# k26_baseboard_connectors2.net
KiCad netlist of a schematic drawn in Altium Designer
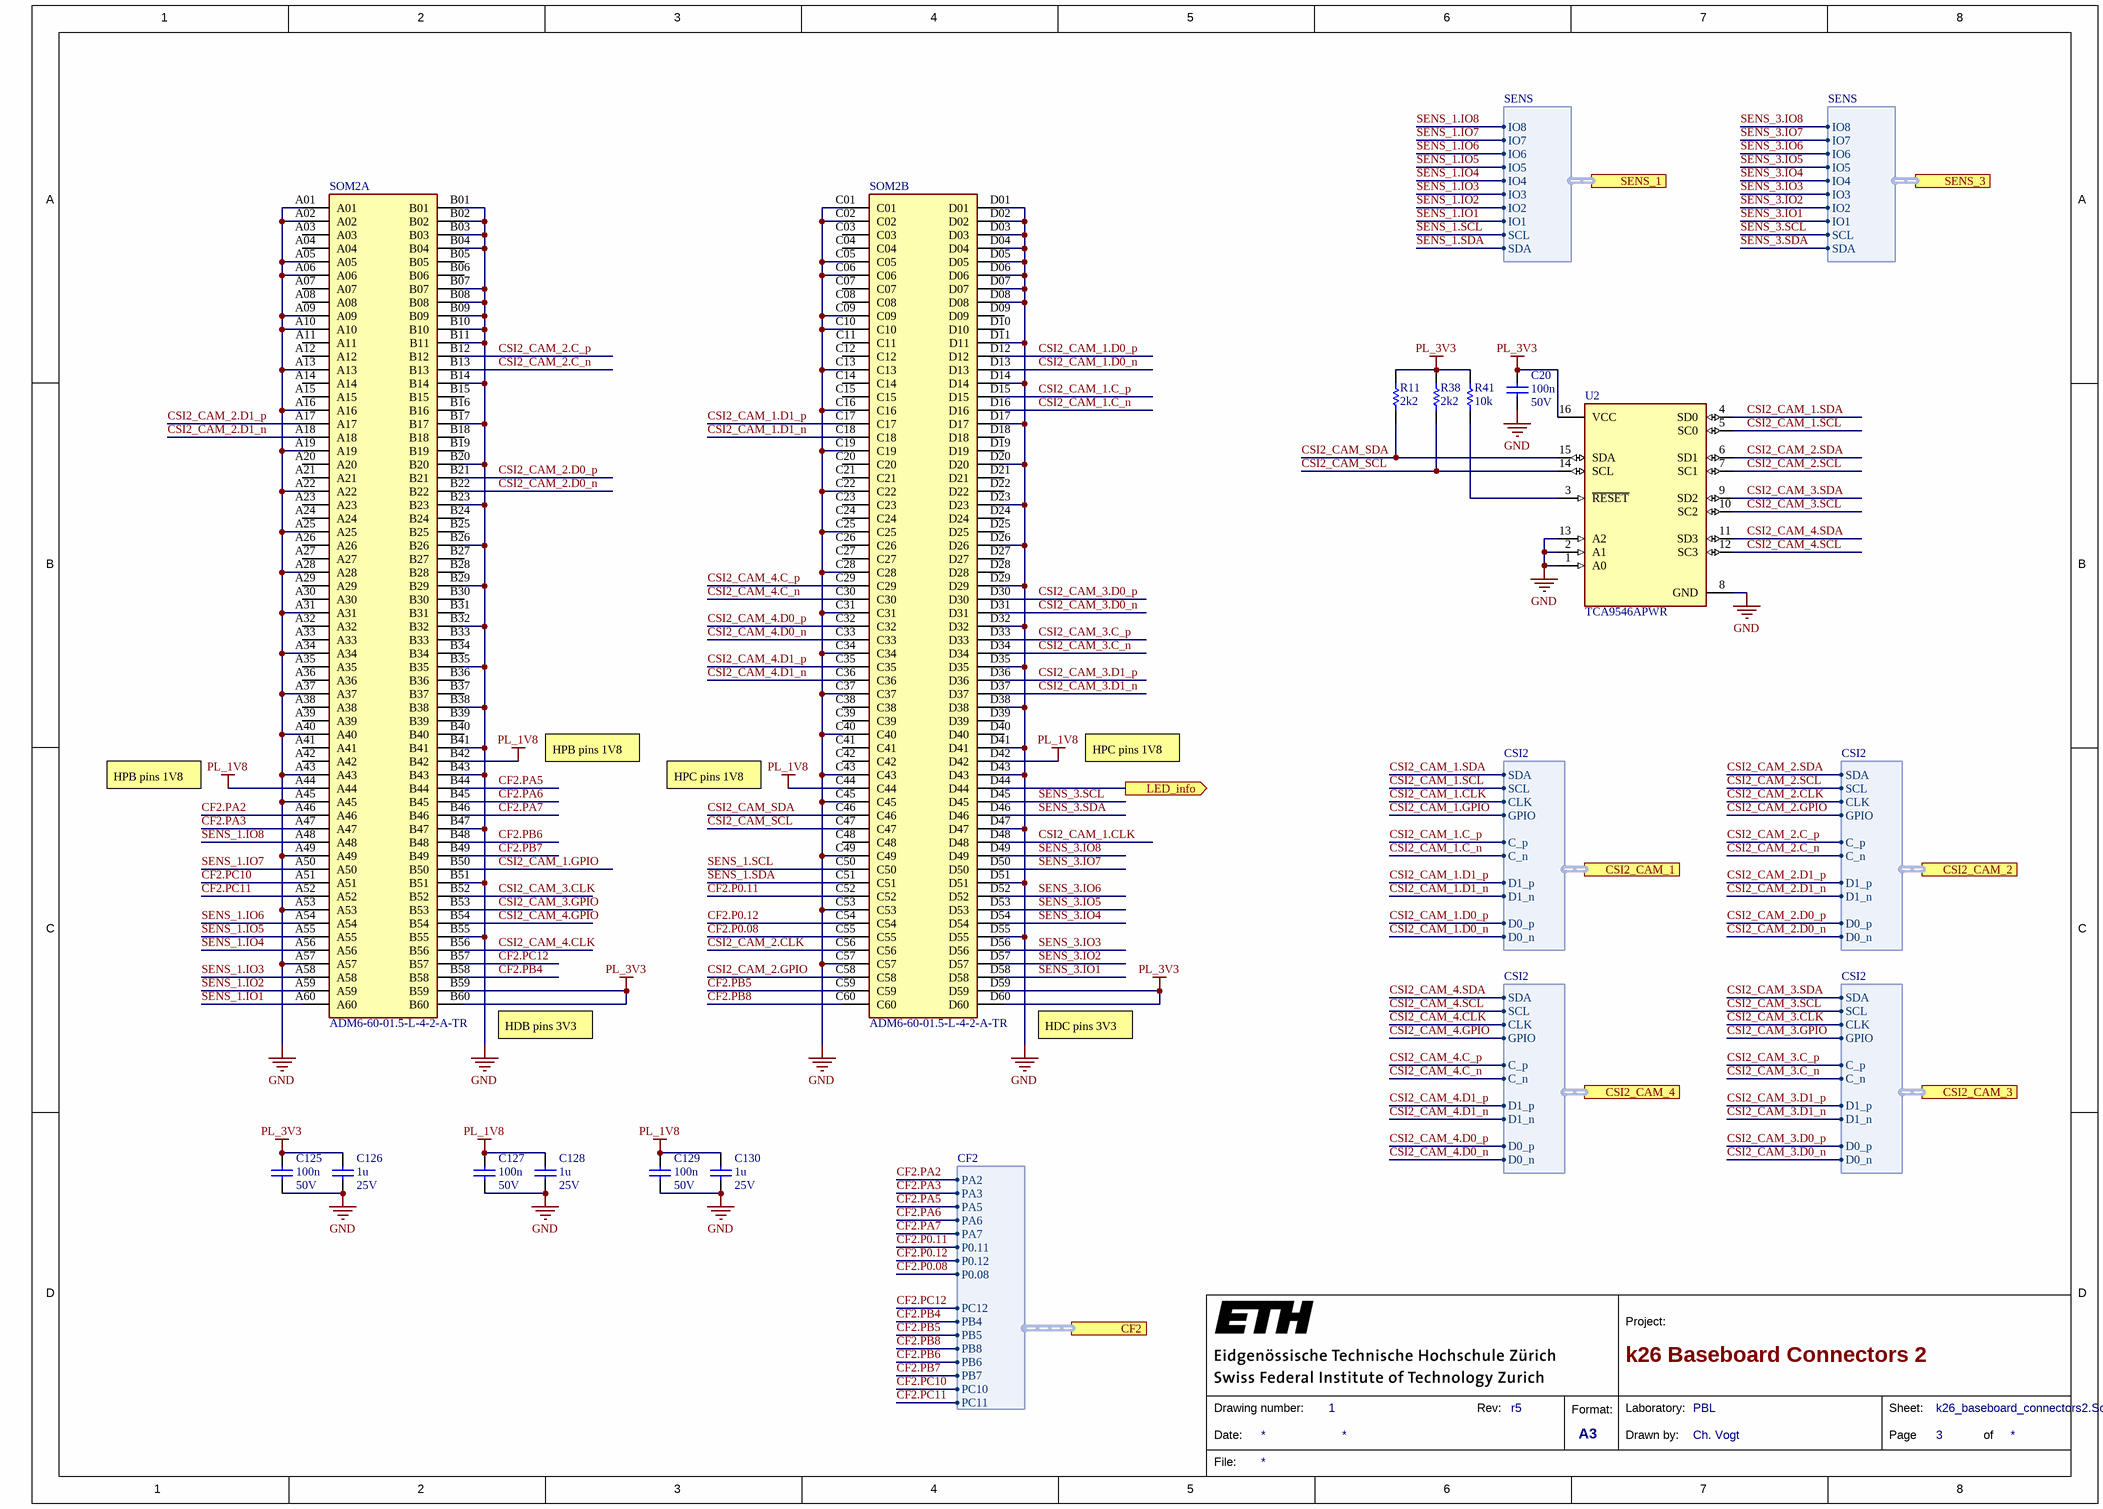
[diagram p0: k26_baseboard_connectors2.SchDoc]

(export (version "E")
  (design (tool "Eeschema 10.0.6"))
  (components
    (comp (ref "C20")
      (value "100n")
      (footprint "k26_FPGA_drone_baseboard:CAPC0402")
      (fields
        (field (name "MANUFACTURER") "Yageo")
        (field (name "MANUFACTURER PART NUMBER") "CC0402KRX5R9BB104")
        (field (name "RATED DC VOLTAGE (URDC)") "50V")
      )
      (libsource (lib "k26_FPGA_drone_baseboard") (part "cap0402"))
    )
    (comp (ref "C125")
      (value "100n")
      (footprint "k26_FPGA_drone_baseboard:CAPC0402")
      (fields
        (field (name "MANUFACTURER") "Yageo")
        (field (name "MANUFACTURER PART NUMBER") "CC0402KRX5R9BB104")
        (field (name "RATED DC VOLTAGE (URDC)") "50V")
      )
      (libsource (lib "k26_FPGA_drone_baseboard") (part "cap0402"))
    )
    (comp (ref "C126")
      (value "1u")
      (footprint "k26_FPGA_drone_baseboard:CAPC0402")
      (fields
        (field (name "MANUFACTURER") "Taiyo Yuden")
        (field (name "MANUFACTURER PART NUMBER") "TMK105BJ105MV-F")
        (field (name "RATED DC VOLTAGE (URDC)") "25V")
      )
      (libsource (lib "k26_FPGA_drone_baseboard") (part "cap0402"))
    )
    (comp (ref "C127")
      (value "100n")
      (footprint "k26_FPGA_drone_baseboard:CAPC0402")
      (fields
        (field (name "MANUFACTURER") "Yageo")
        (field (name "MANUFACTURER PART NUMBER") "CC0402KRX5R9BB104")
        (field (name "RATED DC VOLTAGE (URDC)") "50V")
      )
      (libsource (lib "k26_FPGA_drone_baseboard") (part "cap0402"))
    )
    (comp (ref "C128")
      (value "1u")
      (footprint "k26_FPGA_drone_baseboard:CAPC0402")
      (fields
        (field (name "MANUFACTURER") "Taiyo Yuden")
        (field (name "MANUFACTURER PART NUMBER") "TMK105BJ105MV-F")
        (field (name "RATED DC VOLTAGE (URDC)") "25V")
      )
      (libsource (lib "k26_FPGA_drone_baseboard") (part "cap0402"))
    )
    (comp (ref "C129")
      (value "100n")
      (footprint "k26_FPGA_drone_baseboard:CAPC0402")
      (fields
        (field (name "MANUFACTURER") "Yageo")
        (field (name "MANUFACTURER PART NUMBER") "CC0402KRX5R9BB104")
        (field (name "RATED DC VOLTAGE (URDC)") "50V")
      )
      (libsource (lib "k26_FPGA_drone_baseboard") (part "cap0402"))
    )
    (comp (ref "C130")
      (value "1u")
      (footprint "k26_FPGA_drone_baseboard:CAPC0402")
      (fields
        (field (name "MANUFACTURER") "Taiyo Yuden")
        (field (name "MANUFACTURER PART NUMBER") "TMK105BJ105MV-F")
        (field (name "RATED DC VOLTAGE (URDC)") "25V")
      )
      (libsource (lib "k26_FPGA_drone_baseboard") (part "cap0402"))
    )
    (comp (ref "R11")
      (value "2k2")
      (footprint "k26_FPGA_drone_baseboard:RES0402")
      (fields
        (field (name "MANUFACTURER") "Vishay")
        (field (name "MANUFACTURER PART NUMBER") "CRCW04022K20FKED")
        (field (name "TOLERANCE") "1%")
      )
      (libsource (lib "k26_FPGA_drone_baseboard") (part "res0402"))
    )
    (comp (ref "R38")
      (value "2k2")
      (footprint "k26_FPGA_drone_baseboard:RES0402")
      (fields
        (field (name "MANUFACTURER") "Vishay")
        (field (name "MANUFACTURER PART NUMBER") "CRCW04022K20FKED")
        (field (name "TOLERANCE") "1%")
      )
      (libsource (lib "k26_FPGA_drone_baseboard") (part "res0402"))
    )
    (comp (ref "R41")
      (value "10k")
      (footprint "k26_FPGA_drone_baseboard:RES0402")
      (fields
        (field (name "MANUFACTURER") "Panasonic")
        (field (name "MANUFACTURER PART NUMBER") "ERJ-2RKF1002X")
        (field (name "TOLERANCE") "1%")
      )
      (libsource (lib "k26_FPGA_drone_baseboard") (part "res0402"))
    )
    (comp (ref "SOM2")
      (value "ADM6-60-01.5-L-4-2-A-TR")
      (footprint "k26_FPGA_drone_baseboard:SAMTEC_ADM6-60-01.5-L-4-2-A-TR")
      (description "0.635 mm AcceleRate HD High-Density 4-Row Header")
      (libsource (lib "k26_FPGA_drone_baseboard") (part "ADM6-60-01.5-L-4-2-A-TR"))
    )
    (comp (ref "U2")
      (value "TCA9546APWR")
      (footprint "FP-PW0016A-MFG")
      (description "IC I2C SW 4CH W/RESET 16TSSOP")
      (fields
        (field (name "MANUFACTURER") "Texas Instruments")
        (field (name "OCTOPART") "https://octopart.com/tca9546apwr-texas+instruments-22292132")
      )
      (libsource (lib "Altium Content Vault") (part "b52764720d55b156f509f767142d035"))
    )
  )
  (nets
    (net (code "4") (name "/CF2.P0.08") (class "Default")
      (node (ref "SOM2") (pin "C55") (pinfunction "C55_C55") (pintype "passive"))
    )
    (net (code "5") (name "/CF2.P0.11") (class "Default")
      (node (ref "SOM2") (pin "C52") (pinfunction "C52_C52") (pintype "passive"))
    )
    (net (code "6") (name "/CF2.P0.12") (class "Default")
      (node (ref "SOM2") (pin "C54") (pinfunction "C54_C54") (pintype "passive"))
    )
    (net (code "7") (name "/CF2.PA2") (class "Default")
      (node (ref "SOM2") (pin "A46") (pinfunction "A46_A46") (pintype "passive"))
    )
    (net (code "8") (name "/CF2.PA3") (class "Default")
      (node (ref "SOM2") (pin "A47") (pinfunction "A47_A47") (pintype "passive"))
    )
    (net (code "9") (name "/CF2.PA5") (class "Default")
      (node (ref "SOM2") (pin "B44") (pinfunction "B44_B44") (pintype "passive"))
    )
    (net (code "10") (name "/CF2.PA6") (class "Default")
      (node (ref "SOM2") (pin "B45") (pinfunction "B45_B45") (pintype "passive"))
    )
    (net (code "11") (name "/CF2.PA7") (class "Default")
      (node (ref "SOM2") (pin "B46") (pinfunction "B46_B46") (pintype "passive"))
    )
    (net (code "12") (name "/CF2.PB4") (class "Default")
      (node (ref "SOM2") (pin "B58") (pinfunction "B58_B58") (pintype "passive"))
    )
    (net (code "13") (name "/CF2.PB5") (class "Default")
      (node (ref "SOM2") (pin "C59") (pinfunction "C59_C59") (pintype "passive"))
    )
    (net (code "14") (name "/CF2.PB6") (class "Default")
      (node (ref "SOM2") (pin "B48") (pinfunction "B48_B48") (pintype "passive"))
    )
    (net (code "15") (name "/CF2.PB7") (class "Default")
      (node (ref "SOM2") (pin "B49") (pinfunction "B49_B49") (pintype "passive"))
    )
    (net (code "16") (name "/CF2.PB8") (class "Default")
      (node (ref "SOM2") (pin "C60") (pinfunction "C60_C60") (pintype "passive"))
    )
    (net (code "17") (name "/CF2.PC10") (class "Default")
      (node (ref "SOM2") (pin "A51") (pinfunction "A51_A51") (pintype "passive"))
    )
    (net (code "18") (name "/CF2.PC11") (class "Default")
      (node (ref "SOM2") (pin "A52") (pinfunction "A52_A52") (pintype "passive"))
    )
    (net (code "19") (name "/CF2.PC12") (class "Default")
      (node (ref "SOM2") (pin "B57") (pinfunction "B57_B57") (pintype "passive"))
    )
    (net (code "20") (name "/CSI2_CAM_1.CLK") (class "Default")
      (node (ref "SOM2") (pin "D48") (pinfunction "D48_D48") (pintype "passive"))
    )
    (net (code "21") (name "/CSI2_CAM_1.C_n") (class "Default")
      (node (ref "SOM2") (pin "D16") (pinfunction "D16_D16") (pintype "passive"))
    )
    (net (code "22") (name "/CSI2_CAM_1.C_p") (class "Default")
      (node (ref "SOM2") (pin "D15") (pinfunction "D15_D15") (pintype "passive"))
    )
    (net (code "23") (name "/CSI2_CAM_1.D0_n") (class "Default")
      (node (ref "SOM2") (pin "D13") (pinfunction "D13_D13") (pintype "passive"))
    )
    (net (code "24") (name "/CSI2_CAM_1.D0_p") (class "Default")
      (node (ref "SOM2") (pin "D12") (pinfunction "D12_D12") (pintype "passive"))
    )
    (net (code "25") (name "/CSI2_CAM_1.D1_n") (class "Default")
      (node (ref "SOM2") (pin "C18") (pinfunction "C18_C18") (pintype "passive"))
    )
    (net (code "26") (name "/CSI2_CAM_1.D1_p") (class "Default")
      (node (ref "SOM2") (pin "C17") (pinfunction "C17_C17") (pintype "passive"))
    )
    (net (code "27") (name "/CSI2_CAM_1.GPIO") (class "Default")
      (node (ref "SOM2") (pin "B50") (pinfunction "B50_B50") (pintype "passive"))
    )
    (net (code "28") (name "/CSI2_CAM_1.SCL") (class "Default")
      (node (ref "U2") (pin "5") (pinfunction "SC0_5") (pintype "bidirectional"))
    )
    (net (code "29") (name "/CSI2_CAM_1.SDA") (class "Default")
      (node (ref "U2") (pin "4") (pinfunction "SD0_4") (pintype "bidirectional"))
    )
    (net (code "30") (name "/CSI2_CAM_2.CLK") (class "Default")
      (node (ref "SOM2") (pin "C56") (pinfunction "C56_C56") (pintype "passive"))
    )
    (net (code "31") (name "/CSI2_CAM_2.C_n") (class "Default")
      (node (ref "SOM2") (pin "B13") (pinfunction "B13_B13") (pintype "passive"))
    )
    (net (code "32") (name "/CSI2_CAM_2.C_p") (class "Default")
      (node (ref "SOM2") (pin "B12") (pinfunction "B12_B12") (pintype "passive"))
    )
    (net (code "33") (name "/CSI2_CAM_2.D0_n") (class "Default")
      (node (ref "SOM2") (pin "B22") (pinfunction "B22_B22") (pintype "passive"))
    )
    (net (code "34") (name "/CSI2_CAM_2.D0_p") (class "Default")
      (node (ref "SOM2") (pin "B21") (pinfunction "B21_B21") (pintype "passive"))
    )
    (net (code "35") (name "/CSI2_CAM_2.D1_n") (class "Default")
      (node (ref "SOM2") (pin "A18") (pinfunction "A18_A18") (pintype "passive"))
    )
    (net (code "36") (name "/CSI2_CAM_2.D1_p") (class "Default")
      (node (ref "SOM2") (pin "A17") (pinfunction "A17_A17") (pintype "passive"))
    )
    (net (code "37") (name "/CSI2_CAM_2.GPIO") (class "Default")
      (node (ref "SOM2") (pin "C58") (pinfunction "C58_C58") (pintype "passive"))
    )
    (net (code "38") (name "/CSI2_CAM_2.SCL") (class "Default")
      (node (ref "U2") (pin "7") (pinfunction "SC1_7") (pintype "bidirectional"))
    )
    (net (code "39") (name "/CSI2_CAM_2.SDA") (class "Default")
      (node (ref "U2") (pin "6") (pinfunction "SD1_6") (pintype "bidirectional"))
    )
    (net (code "40") (name "/CSI2_CAM_3.CLK") (class "Default")
      (node (ref "SOM2") (pin "B52") (pinfunction "B52_B52") (pintype "passive"))
    )
    (net (code "41") (name "/CSI2_CAM_3.C_n") (class "Default")
      (node (ref "SOM2") (pin "D34") (pinfunction "D34_D34") (pintype "passive"))
    )
    (net (code "42") (name "/CSI2_CAM_3.C_p") (class "Default")
      (node (ref "SOM2") (pin "D33") (pinfunction "D33_D33") (pintype "passive"))
    )
    (net (code "43") (name "/CSI2_CAM_3.D0_n") (class "Default")
      (node (ref "SOM2") (pin "D31") (pinfunction "D31_D31") (pintype "passive"))
    )
    (net (code "44") (name "/CSI2_CAM_3.D0_p") (class "Default")
      (node (ref "SOM2") (pin "D30") (pinfunction "D30_D30") (pintype "passive"))
    )
    (net (code "45") (name "/CSI2_CAM_3.D1_n") (class "Default")
      (node (ref "SOM2") (pin "D37") (pinfunction "D37_D37") (pintype "passive"))
    )
    (net (code "46") (name "/CSI2_CAM_3.D1_p") (class "Default")
      (node (ref "SOM2") (pin "D36") (pinfunction "D36_D36") (pintype "passive"))
    )
    (net (code "47") (name "/CSI2_CAM_3.GPIO") (class "Default")
      (node (ref "SOM2") (pin "B53") (pinfunction "B53_B53") (pintype "passive"))
    )
    (net (code "48") (name "/CSI2_CAM_3.SCL") (class "Default")
      (node (ref "U2") (pin "10") (pinfunction "SC2_10") (pintype "bidirectional"))
    )
    (net (code "49") (name "/CSI2_CAM_3.SDA") (class "Default")
      (node (ref "U2") (pin "9") (pinfunction "SD2_9") (pintype "bidirectional"))
    )
    (net (code "50") (name "/CSI2_CAM_4.CLK") (class "Default")
      (node (ref "SOM2") (pin "B56") (pinfunction "B56_B56") (pintype "passive"))
    )
    (net (code "51") (name "/CSI2_CAM_4.C_n") (class "Default")
      (node (ref "SOM2") (pin "C30") (pinfunction "C30_C30") (pintype "passive"))
    )
    (net (code "52") (name "/CSI2_CAM_4.C_p") (class "Default")
      (node (ref "SOM2") (pin "C29") (pinfunction "C29_C29") (pintype "passive"))
    )
    (net (code "53") (name "/CSI2_CAM_4.D0_n") (class "Default")
      (node (ref "SOM2") (pin "C33") (pinfunction "C33_C33") (pintype "passive"))
    )
    (net (code "54") (name "/CSI2_CAM_4.D0_p") (class "Default")
      (node (ref "SOM2") (pin "C32") (pinfunction "C32_C32") (pintype "passive"))
    )
    (net (code "55") (name "/CSI2_CAM_4.D1_n") (class "Default")
      (node (ref "SOM2") (pin "C36") (pinfunction "C36_C36") (pintype "passive"))
    )
    (net (code "56") (name "/CSI2_CAM_4.D1_p") (class "Default")
      (node (ref "SOM2") (pin "C35") (pinfunction "C35_C35") (pintype "passive"))
    )
    (net (code "57") (name "/CSI2_CAM_4.GPIO") (class "Default")
      (node (ref "SOM2") (pin "B54") (pinfunction "B54_B54") (pintype "passive"))
    )
    (net (code "58") (name "/CSI2_CAM_4.SCL") (class "Default")
      (node (ref "U2") (pin "12") (pinfunction "SC3_12") (pintype "bidirectional"))
    )
    (net (code "59") (name "/CSI2_CAM_4.SDA") (class "Default")
      (node (ref "U2") (pin "11") (pinfunction "SD3_11") (pintype "bidirectional"))
    )
    (net (code "60") (name "/CSI2_CAM_SCL") (class "Default")
      (node (ref "R38") (pin "1") (pinfunction "1_1") (pintype "passive"))
      (node (ref "SOM2") (pin "C47") (pinfunction "C47_C47") (pintype "passive"))
      (node (ref "U2") (pin "14") (pinfunction "SCL_14") (pintype "bidirectional"))
    )
    (net (code "61") (name "/CSI2_CAM_SDA") (class "Default")
      (node (ref "R11") (pin "1") (pinfunction "1_1") (pintype "passive"))
      (node (ref "SOM2") (pin "C46") (pinfunction "C46_C46") (pintype "passive"))
      (node (ref "U2") (pin "15") (pinfunction "SDA_15") (pintype "bidirectional"))
    )
    (net (code "62") (name "/LED_info") (class "Default")
      (node (ref "SOM2") (pin "D44") (pinfunction "D44_D44") (pintype "passive"))
    )
    (net (code "63") (name "/SENS_1.IO1") (class "Default")
      (node (ref "SOM2") (pin "A60") (pinfunction "A60_A60") (pintype "passive"))
    )
    (net (code "64") (name "/SENS_1.IO2") (class "Default")
      (node (ref "SOM2") (pin "A59") (pinfunction "A59_A59") (pintype "passive"))
    )
    (net (code "65") (name "/SENS_1.IO3") (class "Default")
      (node (ref "SOM2") (pin "A58") (pinfunction "A58_A58") (pintype "passive"))
    )
    (net (code "66") (name "/SENS_1.IO4") (class "Default")
      (node (ref "SOM2") (pin "A56") (pinfunction "A56_A56") (pintype "passive"))
    )
    (net (code "67") (name "/SENS_1.IO5") (class "Default")
      (node (ref "SOM2") (pin "A55") (pinfunction "A55_A55") (pintype "passive"))
    )
    (net (code "68") (name "/SENS_1.IO6") (class "Default")
      (node (ref "SOM2") (pin "A54") (pinfunction "A54_A54") (pintype "passive"))
    )
    (net (code "69") (name "/SENS_1.IO7") (class "Default")
      (node (ref "SOM2") (pin "A50") (pinfunction "A50_A50") (pintype "passive"))
    )
    (net (code "70") (name "/SENS_1.IO8") (class "Default")
      (node (ref "SOM2") (pin "A48") (pinfunction "A48_A48") (pintype "passive"))
    )
    (net (code "71") (name "/SENS_1.SCL") (class "Default")
      (node (ref "SOM2") (pin "C50") (pinfunction "C50_C50") (pintype "passive"))
    )
    (net (code "72") (name "/SENS_1.SDA") (class "Default")
      (node (ref "SOM2") (pin "C51") (pinfunction "C51_C51") (pintype "passive"))
    )
    (net (code "73") (name "/SENS_3.IO1") (class "Default")
      (node (ref "SOM2") (pin "D58") (pinfunction "D58_D58") (pintype "passive"))
    )
    (net (code "74") (name "/SENS_3.IO2") (class "Default")
      (node (ref "SOM2") (pin "D57") (pinfunction "D57_D57") (pintype "passive"))
    )
    (net (code "75") (name "/SENS_3.IO3") (class "Default")
      (node (ref "SOM2") (pin "D56") (pinfunction "D56_D56") (pintype "passive"))
    )
    (net (code "76") (name "/SENS_3.IO4") (class "Default")
      (node (ref "SOM2") (pin "D54") (pinfunction "D54_D54") (pintype "passive"))
    )
    (net (code "77") (name "/SENS_3.IO5") (class "Default")
      (node (ref "SOM2") (pin "D53") (pinfunction "D53_D53") (pintype "passive"))
    )
    (net (code "78") (name "/SENS_3.IO6") (class "Default")
      (node (ref "SOM2") (pin "D52") (pinfunction "D52_D52") (pintype "passive"))
    )
    (net (code "79") (name "/SENS_3.IO7") (class "Default")
      (node (ref "SOM2") (pin "D50") (pinfunction "D50_D50") (pintype "passive"))
    )
    (net (code "80") (name "/SENS_3.IO8") (class "Default")
      (node (ref "SOM2") (pin "D49") (pinfunction "D49_D49") (pintype "passive"))
    )
    (net (code "81") (name "/SENS_3.SCL") (class "Default")
      (node (ref "SOM2") (pin "D45") (pinfunction "D45_D45") (pintype "passive"))
    )
    (net (code "82") (name "/SENS_3.SDA") (class "Default")
      (node (ref "SOM2") (pin "D46") (pinfunction "D46_D46") (pintype "passive"))
    )
    (net (code "86") (name "GND") (class "Default")
      (node (ref "C125") (pin "1") (pinfunction "1_1") (pintype "passive"))
      (node (ref "C126") (pin "1") (pinfunction "1_1") (pintype "passive"))
      (node (ref "C127") (pin "1") (pinfunction "1_1") (pintype "passive"))
      (node (ref "C128") (pin "1") (pinfunction "1_1") (pintype "passive"))
      (node (ref "C129") (pin "1") (pinfunction "1_1") (pintype "passive"))
      (node (ref "C130") (pin "1") (pinfunction "1_1") (pintype "passive"))
      (node (ref "C20") (pin "1") (pinfunction "1_1") (pintype "passive"))
      (node (ref "SOM2") (pin "A01") (pinfunction "A01_A01") (pintype "passive"))
      (node (ref "SOM2") (pin "A02") (pinfunction "A02_A02") (pintype "passive"))
      (node (ref "SOM2") (pin "A05") (pinfunction "A05_A05") (pintype "passive"))
      (node (ref "SOM2") (pin "A06") (pinfunction "A06_A06") (pintype "passive"))
      (node (ref "SOM2") (pin "A09") (pinfunction "A09_A09") (pintype "passive"))
      (node (ref "SOM2") (pin "A10") (pinfunction "A10_A10") (pintype "passive"))
      (node (ref "SOM2") (pin "A13") (pinfunction "A13_A13") (pintype "passive"))
      (node (ref "SOM2") (pin "A16") (pinfunction "A16_A16") (pintype "passive"))
      (node (ref "SOM2") (pin "A19") (pinfunction "A19_A19") (pintype "passive"))
      (node (ref "SOM2") (pin "A22") (pinfunction "A22_A22") (pintype "passive"))
      (node (ref "SOM2") (pin "A25") (pinfunction "A25_A25") (pintype "passive"))
      (node (ref "SOM2") (pin "A28") (pinfunction "A28_A28") (pintype "passive"))
      (node (ref "SOM2") (pin "A31") (pinfunction "A31_A31") (pintype "passive"))
      (node (ref "SOM2") (pin "A34") (pinfunction "A34_A34") (pintype "passive"))
      (node (ref "SOM2") (pin "A37") (pinfunction "A37_A37") (pintype "passive"))
      (node (ref "SOM2") (pin "A40") (pinfunction "A40_A40") (pintype "passive"))
      (node (ref "SOM2") (pin "A43") (pinfunction "A43_A43") (pintype "passive"))
      (node (ref "SOM2") (pin "A45") (pinfunction "A45_A45") (pintype "passive"))
      (node (ref "SOM2") (pin "A49") (pinfunction "A49_A49") (pintype "passive"))
      (node (ref "SOM2") (pin "A53") (pinfunction "A53_A53") (pintype "passive"))
      (node (ref "SOM2") (pin "A57") (pinfunction "A57_A57") (pintype "passive"))
      (node (ref "SOM2") (pin "B01") (pinfunction "B01_B01") (pintype "passive"))
      (node (ref "SOM2") (pin "B02") (pinfunction "B02_B02") (pintype "passive"))
      (node (ref "SOM2") (pin "B03") (pinfunction "B03_B03") (pintype "passive"))
      (node (ref "SOM2") (pin "B04") (pinfunction "B04_B04") (pintype "passive"))
      (node (ref "SOM2") (pin "B07") (pinfunction "B07_B07") (pintype "passive"))
      (node (ref "SOM2") (pin "B08") (pinfunction "B08_B08") (pintype "passive"))
      (node (ref "SOM2") (pin "B09") (pinfunction "B09_B09") (pintype "passive"))
      (node (ref "SOM2") (pin "B10") (pinfunction "B10_B10") (pintype "passive"))
      (node (ref "SOM2") (pin "B11") (pinfunction "B11_B11") (pintype "passive"))
      (node (ref "SOM2") (pin "B14") (pinfunction "B14_B14") (pintype "passive"))
      (node (ref "SOM2") (pin "B17") (pinfunction "B17_B17") (pintype "passive"))
      (node (ref "SOM2") (pin "B20") (pinfunction "B20_B20") (pintype "passive"))
      (node (ref "SOM2") (pin "B23") (pinfunction "B23_B23") (pintype "passive"))
      (node (ref "SOM2") (pin "B26") (pinfunction "B26_B26") (pintype "passive"))
      (node (ref "SOM2") (pin "B29") (pinfunction "B29_B29") (pintype "passive"))
      (node (ref "SOM2") (pin "B32") (pinfunction "B32_B32") (pintype "passive"))
      (node (ref "SOM2") (pin "B35") (pinfunction "B35_B35") (pintype "passive"))
      (node (ref "SOM2") (pin "B38") (pinfunction "B38_B38") (pintype "passive"))
      (node (ref "SOM2") (pin "B41") (pinfunction "B41_B41") (pintype "passive"))
      (node (ref "SOM2") (pin "B43") (pinfunction "B43_B43") (pintype "passive"))
      (node (ref "SOM2") (pin "B47") (pinfunction "B47_B47") (pintype "passive"))
      (node (ref "SOM2") (pin "B51") (pinfunction "B51_B51") (pintype "passive"))
      (node (ref "SOM2") (pin "B55") (pinfunction "B55_B55") (pintype "passive"))
      (node (ref "SOM2") (pin "C01") (pinfunction "C01_C01") (pintype "passive"))
      (node (ref "SOM2") (pin "C02") (pinfunction "C02_C02") (pintype "passive"))
      (node (ref "SOM2") (pin "C05") (pinfunction "C05_C05") (pintype "passive"))
      (node (ref "SOM2") (pin "C06") (pinfunction "C06_C06") (pintype "passive"))
      (node (ref "SOM2") (pin "C09") (pinfunction "C09_C09") (pintype "passive"))
      (node (ref "SOM2") (pin "C10") (pinfunction "C10_C10") (pintype "passive"))
      (node (ref "SOM2") (pin "C13") (pinfunction "C13_C13") (pintype "passive"))
      (node (ref "SOM2") (pin "C16") (pinfunction "C16_C16") (pintype "passive"))
      (node (ref "SOM2") (pin "C19") (pinfunction "C19_C19") (pintype "passive"))
      (node (ref "SOM2") (pin "C22") (pinfunction "C22_C22") (pintype "passive"))
      (node (ref "SOM2") (pin "C25") (pinfunction "C25_C25") (pintype "passive"))
      (node (ref "SOM2") (pin "C28") (pinfunction "C28_C28") (pintype "passive"))
      (node (ref "SOM2") (pin "C31") (pinfunction "C31_C31") (pintype "passive"))
      (node (ref "SOM2") (pin "C34") (pinfunction "C34_C34") (pintype "passive"))
      (node (ref "SOM2") (pin "C37") (pinfunction "C37_C37") (pintype "passive"))
      (node (ref "SOM2") (pin "C40") (pinfunction "C40_C40") (pintype "passive"))
      (node (ref "SOM2") (pin "C43") (pinfunction "C43_C43") (pintype "passive"))
      (node (ref "SOM2") (pin "C45") (pinfunction "C45_C45") (pintype "passive"))
      (node (ref "SOM2") (pin "C49") (pinfunction "C49_C49") (pintype "passive"))
      (node (ref "SOM2") (pin "C53") (pinfunction "C53_C53") (pintype "passive"))
      (node (ref "SOM2") (pin "C57") (pinfunction "C57_C57") (pintype "passive"))
      (node (ref "SOM2") (pin "D01") (pinfunction "D01_D01") (pintype "passive"))
      (node (ref "SOM2") (pin "D02") (pinfunction "D02_D02") (pintype "passive"))
      (node (ref "SOM2") (pin "D03") (pinfunction "D03_D03") (pintype "passive"))
      (node (ref "SOM2") (pin "D04") (pinfunction "D04_D04") (pintype "passive"))
      (node (ref "SOM2") (pin "D05") (pinfunction "D05_D05") (pintype "passive"))
      (node (ref "SOM2") (pin "D06") (pinfunction "D06_D06") (pintype "passive"))
      (node (ref "SOM2") (pin "D07") (pinfunction "D07_D07") (pintype "passive"))
      (node (ref "SOM2") (pin "D08") (pinfunction "D08_D08") (pintype "passive"))
      (node (ref "SOM2") (pin "D11") (pinfunction "D11_D11") (pintype "passive"))
      (node (ref "SOM2") (pin "D14") (pinfunction "D14_D14") (pintype "passive"))
      (node (ref "SOM2") (pin "D17") (pinfunction "D17_D17") (pintype "passive"))
      (node (ref "SOM2") (pin "D20") (pinfunction "D20_D20") (pintype "passive"))
      (node (ref "SOM2") (pin "D23") (pinfunction "D23_D23") (pintype "passive"))
      (node (ref "SOM2") (pin "D26") (pinfunction "D26_D26") (pintype "passive"))
      (node (ref "SOM2") (pin "D29") (pinfunction "D29_D29") (pintype "passive"))
      (node (ref "SOM2") (pin "D32") (pinfunction "D32_D32") (pintype "passive"))
      (node (ref "SOM2") (pin "D35") (pinfunction "D35_D35") (pintype "passive"))
      (node (ref "SOM2") (pin "D38") (pinfunction "D38_D38") (pintype "passive"))
      (node (ref "SOM2") (pin "D41") (pinfunction "D41_D41") (pintype "passive"))
      (node (ref "SOM2") (pin "D43") (pinfunction "D43_D43") (pintype "passive"))
      (node (ref "SOM2") (pin "D47") (pinfunction "D47_D47") (pintype "passive"))
      (node (ref "SOM2") (pin "D51") (pinfunction "D51_D51") (pintype "passive"))
      (node (ref "SOM2") (pin "D55") (pinfunction "D55_D55") (pintype "passive"))
      (node (ref "U2") (pin "1") (pinfunction "A0_1") (pintype "input"))
      (node (ref "U2") (pin "13") (pinfunction "A2_13") (pintype "input"))
      (node (ref "U2") (pin "2") (pinfunction "A1_2") (pintype "input"))
      (node (ref "U2") (pin "8") (pinfunction "GND_8") (pintype "power_in"))
    )
    (net (code "87") (name "Net-(U2-~{RESET})") (class "Default")
      (node (ref "R41") (pin "1") (pinfunction "1_1") (pintype "passive"))
      (node (ref "U2") (pin "3") (pinfunction "~{RESET}_3") (pintype "input"))
    )
    (net (code "88") (name "PL_1V8") (class "Default")
      (node (ref "C127") (pin "2") (pinfunction "2_2") (pintype "passive"))
      (node (ref "C128") (pin "2") (pinfunction "2_2") (pintype "passive"))
      (node (ref "C129") (pin "2") (pinfunction "2_2") (pintype "passive"))
      (node (ref "C130") (pin "2") (pinfunction "2_2") (pintype "passive"))
      (node (ref "SOM2") (pin "A44") (pinfunction "A44_A44") (pintype "passive"))
      (node (ref "SOM2") (pin "B42") (pinfunction "B42_B42") (pintype "passive"))
      (node (ref "SOM2") (pin "C44") (pinfunction "C44_C44") (pintype "passive"))
      (node (ref "SOM2") (pin "D42") (pinfunction "D42_D42") (pintype "passive"))
    )
    (net (code "89") (name "PL_3V3") (class "Default")
      (node (ref "C125") (pin "2") (pinfunction "2_2") (pintype "passive"))
      (node (ref "C126") (pin "2") (pinfunction "2_2") (pintype "passive"))
      (node (ref "C20") (pin "2") (pinfunction "2_2") (pintype "passive"))
      (node (ref "R11") (pin "2") (pinfunction "2_2") (pintype "passive"))
      (node (ref "R38") (pin "2") (pinfunction "2_2") (pintype "passive"))
      (node (ref "R41") (pin "2") (pinfunction "2_2") (pintype "passive"))
      (node (ref "SOM2") (pin "B59") (pinfunction "B59_B59") (pintype "passive"))
      (node (ref "SOM2") (pin "B60") (pinfunction "B60_B60") (pintype "passive"))
      (node (ref "SOM2") (pin "D59") (pinfunction "D59_D59") (pintype "passive"))
      (node (ref "SOM2") (pin "D60") (pinfunction "D60_D60") (pintype "passive"))
      (node (ref "U2") (pin "16") (pinfunction "VCC_16") (pintype "power_in"))
    )
    (net (code "90") (name "unconnected-(SOM2-PadA03)") (class "Default")
      (node (ref "SOM2") (pin "A03") (pinfunction "A03_A03") (pintype "passive"))
    )
    (net (code "91") (name "unconnected-(SOM2-PadA04)") (class "Default")
      (node (ref "SOM2") (pin "A04") (pinfunction "A04_A04") (pintype "passive"))
    )
    (net (code "92") (name "unconnected-(SOM2-PadA07)") (class "Default")
      (node (ref "SOM2") (pin "A07") (pinfunction "A07_A07") (pintype "passive"))
    )
    (net (code "93") (name "unconnected-(SOM2-PadA08)") (class "Default")
      (node (ref "SOM2") (pin "A08") (pinfunction "A08_A08") (pintype "passive"))
    )
    (net (code "94") (name "unconnected-(SOM2-PadA11)") (class "Default")
      (node (ref "SOM2") (pin "A11") (pinfunction "A11_A11") (pintype "passive"))
    )
    (net (code "95") (name "unconnected-(SOM2-PadA12)") (class "Default")
      (node (ref "SOM2") (pin "A12") (pinfunction "A12_A12") (pintype "passive"))
    )
    (net (code "96") (name "unconnected-(SOM2-PadA14)") (class "Default")
      (node (ref "SOM2") (pin "A14") (pinfunction "A14_A14") (pintype "passive"))
    )
    (net (code "97") (name "unconnected-(SOM2-PadA15)") (class "Default")
      (node (ref "SOM2") (pin "A15") (pinfunction "A15_A15") (pintype "passive"))
    )
    (net (code "98") (name "unconnected-(SOM2-PadA20)") (class "Default")
      (node (ref "SOM2") (pin "A20") (pinfunction "A20_A20") (pintype "passive"))
    )
    (net (code "99") (name "unconnected-(SOM2-PadA21)") (class "Default")
      (node (ref "SOM2") (pin "A21") (pinfunction "A21_A21") (pintype "passive"))
    )
    (net (code "100") (name "unconnected-(SOM2-PadA23)") (class "Default")
      (node (ref "SOM2") (pin "A23") (pinfunction "A23_A23") (pintype "passive"))
    )
    (net (code "101") (name "unconnected-(SOM2-PadA24)") (class "Default")
      (node (ref "SOM2") (pin "A24") (pinfunction "A24_A24") (pintype "passive"))
    )
    (net (code "102") (name "unconnected-(SOM2-PadA26)") (class "Default")
      (node (ref "SOM2") (pin "A26") (pinfunction "A26_A26") (pintype "passive"))
    )
    (net (code "103") (name "unconnected-(SOM2-PadA27)") (class "Default")
      (node (ref "SOM2") (pin "A27") (pinfunction "A27_A27") (pintype "passive"))
    )
    (net (code "104") (name "unconnected-(SOM2-PadA29)") (class "Default")
      (node (ref "SOM2") (pin "A29") (pinfunction "A29_A29") (pintype "passive"))
    )
    (net (code "105") (name "unconnected-(SOM2-PadA30)") (class "Default")
      (node (ref "SOM2") (pin "A30") (pinfunction "A30_A30") (pintype "passive"))
    )
    (net (code "106") (name "unconnected-(SOM2-PadA32)") (class "Default")
      (node (ref "SOM2") (pin "A32") (pinfunction "A32_A32") (pintype "passive"))
    )
    (net (code "107") (name "unconnected-(SOM2-PadA33)") (class "Default")
      (node (ref "SOM2") (pin "A33") (pinfunction "A33_A33") (pintype "passive"))
    )
    (net (code "108") (name "unconnected-(SOM2-PadA35)") (class "Default")
      (node (ref "SOM2") (pin "A35") (pinfunction "A35_A35") (pintype "passive"))
    )
    (net (code "109") (name "unconnected-(SOM2-PadA36)") (class "Default")
      (node (ref "SOM2") (pin "A36") (pinfunction "A36_A36") (pintype "passive"))
    )
    (net (code "110") (name "unconnected-(SOM2-PadA38)") (class "Default")
      (node (ref "SOM2") (pin "A38") (pinfunction "A38_A38") (pintype "passive"))
    )
    (net (code "111") (name "unconnected-(SOM2-PadA39)") (class "Default")
      (node (ref "SOM2") (pin "A39") (pinfunction "A39_A39") (pintype "passive"))
    )
    (net (code "112") (name "unconnected-(SOM2-PadA41)") (class "Default")
      (node (ref "SOM2") (pin "A41") (pinfunction "A41_A41") (pintype "passive"))
    )
    (net (code "113") (name "unconnected-(SOM2-PadA42)") (class "Default")
      (node (ref "SOM2") (pin "A42") (pinfunction "A42_A42") (pintype "passive"))
    )
    (net (code "114") (name "unconnected-(SOM2-PadB05)") (class "Default")
      (node (ref "SOM2") (pin "B05") (pinfunction "B05_B05") (pintype "passive"))
    )
    (net (code "115") (name "unconnected-(SOM2-PadB06)") (class "Default")
      (node (ref "SOM2") (pin "B06") (pinfunction "B06_B06") (pintype "passive"))
    )
    (net (code "116") (name "unconnected-(SOM2-PadB15)") (class "Default")
      (node (ref "SOM2") (pin "B15") (pinfunction "B15_B15") (pintype "passive"))
    )
    (net (code "117") (name "unconnected-(SOM2-PadB16)") (class "Default")
      (node (ref "SOM2") (pin "B16") (pinfunction "B16_B16") (pintype "passive"))
    )
    (net (code "118") (name "unconnected-(SOM2-PadB18)") (class "Default")
      (node (ref "SOM2") (pin "B18") (pinfunction "B18_B18") (pintype "passive"))
    )
    (net (code "119") (name "unconnected-(SOM2-PadB19)") (class "Default")
      (node (ref "SOM2") (pin "B19") (pinfunction "B19_B19") (pintype "passive"))
    )
    (net (code "120") (name "unconnected-(SOM2-PadB24)") (class "Default")
      (node (ref "SOM2") (pin "B24") (pinfunction "B24_B24") (pintype "passive"))
    )
    (net (code "121") (name "unconnected-(SOM2-PadB25)") (class "Default")
      (node (ref "SOM2") (pin "B25") (pinfunction "B25_B25") (pintype "passive"))
    )
    (net (code "122") (name "unconnected-(SOM2-PadB27)") (class "Default")
      (node (ref "SOM2") (pin "B27") (pinfunction "B27_B27") (pintype "passive"))
    )
    (net (code "123") (name "unconnected-(SOM2-PadB28)") (class "Default")
      (node (ref "SOM2") (pin "B28") (pinfunction "B28_B28") (pintype "passive"))
    )
    (net (code "124") (name "unconnected-(SOM2-PadB30)") (class "Default")
      (node (ref "SOM2") (pin "B30") (pinfunction "B30_B30") (pintype "passive"))
    )
    (net (code "125") (name "unconnected-(SOM2-PadB31)") (class "Default")
      (node (ref "SOM2") (pin "B31") (pinfunction "B31_B31") (pintype "passive"))
    )
    (net (code "126") (name "unconnected-(SOM2-PadB33)") (class "Default")
      (node (ref "SOM2") (pin "B33") (pinfunction "B33_B33") (pintype "passive"))
    )
    (net (code "127") (name "unconnected-(SOM2-PadB34)") (class "Default")
      (node (ref "SOM2") (pin "B34") (pinfunction "B34_B34") (pintype "passive"))
    )
    (net (code "128") (name "unconnected-(SOM2-PadB36)") (class "Default")
      (node (ref "SOM2") (pin "B36") (pinfunction "B36_B36") (pintype "passive"))
    )
    (net (code "129") (name "unconnected-(SOM2-PadB37)") (class "Default")
      (node (ref "SOM2") (pin "B37") (pinfunction "B37_B37") (pintype "passive"))
    )
    (net (code "130") (name "unconnected-(SOM2-PadB39)") (class "Default")
      (node (ref "SOM2") (pin "B39") (pinfunction "B39_B39") (pintype "passive"))
    )
    (net (code "131") (name "unconnected-(SOM2-PadB40)") (class "Default")
      (node (ref "SOM2") (pin "B40") (pinfunction "B40_B40") (pintype "passive"))
    )
    (net (code "132") (name "unconnected-(SOM2-PadC03)") (class "Default")
      (node (ref "SOM2") (pin "C03") (pinfunction "C03_C03") (pintype "passive"))
    )
    (net (code "133") (name "unconnected-(SOM2-PadC04)") (class "Default")
      (node (ref "SOM2") (pin "C04") (pinfunction "C04_C04") (pintype "passive"))
    )
    (net (code "134") (name "unconnected-(SOM2-PadC07)") (class "Default")
      (node (ref "SOM2") (pin "C07") (pinfunction "C07_C07") (pintype "passive"))
    )
    (net (code "135") (name "unconnected-(SOM2-PadC08)") (class "Default")
      (node (ref "SOM2") (pin "C08") (pinfunction "C08_C08") (pintype "passive"))
    )
    (net (code "136") (name "unconnected-(SOM2-PadC11)") (class "Default")
      (node (ref "SOM2") (pin "C11") (pinfunction "C11_C11") (pintype "passive"))
    )
    (net (code "137") (name "unconnected-(SOM2-PadC12)") (class "Default")
      (node (ref "SOM2") (pin "C12") (pinfunction "C12_C12") (pintype "passive"))
    )
    (net (code "138") (name "unconnected-(SOM2-PadC14)") (class "Default")
      (node (ref "SOM2") (pin "C14") (pinfunction "C14_C14") (pintype "passive"))
    )
    (net (code "139") (name "unconnected-(SOM2-PadC15)") (class "Default")
      (node (ref "SOM2") (pin "C15") (pinfunction "C15_C15") (pintype "passive"))
    )
    (net (code "140") (name "unconnected-(SOM2-PadC20)") (class "Default")
      (node (ref "SOM2") (pin "C20") (pinfunction "C20_C20") (pintype "passive"))
    )
    (net (code "141") (name "unconnected-(SOM2-PadC21)") (class "Default")
      (node (ref "SOM2") (pin "C21") (pinfunction "C21_C21") (pintype "passive"))
    )
    (net (code "142") (name "unconnected-(SOM2-PadC23)") (class "Default")
      (node (ref "SOM2") (pin "C23") (pinfunction "C23_C23") (pintype "passive"))
    )
    (net (code "143") (name "unconnected-(SOM2-PadC24)") (class "Default")
      (node (ref "SOM2") (pin "C24") (pinfunction "C24_C24") (pintype "passive"))
    )
    (net (code "144") (name "unconnected-(SOM2-PadC26)") (class "Default")
      (node (ref "SOM2") (pin "C26") (pinfunction "C26_C26") (pintype "passive"))
    )
    (net (code "145") (name "unconnected-(SOM2-PadC27)") (class "Default")
      (node (ref "SOM2") (pin "C27") (pinfunction "C27_C27") (pintype "passive"))
    )
    (net (code "146") (name "unconnected-(SOM2-PadC38)") (class "Default")
      (node (ref "SOM2") (pin "C38") (pinfunction "C38_C38") (pintype "passive"))
    )
    (net (code "147") (name "unconnected-(SOM2-PadC39)") (class "Default")
      (node (ref "SOM2") (pin "C39") (pinfunction "C39_C39") (pintype "passive"))
    )
    (net (code "148") (name "unconnected-(SOM2-PadC41)") (class "Default")
      (node (ref "SOM2") (pin "C41") (pinfunction "C41_C41") (pintype "passive"))
    )
    (net (code "149") (name "unconnected-(SOM2-PadC42)") (class "Default")
      (node (ref "SOM2") (pin "C42") (pinfunction "C42_C42") (pintype "passive"))
    )
    (net (code "150") (name "unconnected-(SOM2-PadC48)") (class "Default")
      (node (ref "SOM2") (pin "C48") (pinfunction "C48_C48") (pintype "passive"))
    )
    (net (code "151") (name "unconnected-(SOM2-PadD09)") (class "Default")
      (node (ref "SOM2") (pin "D09") (pinfunction "D09_D09") (pintype "passive"))
    )
    (net (code "152") (name "unconnected-(SOM2-PadD10)") (class "Default")
      (node (ref "SOM2") (pin "D10") (pinfunction "D10_D10") (pintype "passive"))
    )
    (net (code "153") (name "unconnected-(SOM2-PadD18)") (class "Default")
      (node (ref "SOM2") (pin "D18") (pinfunction "D18_D18") (pintype "passive"))
    )
    (net (code "154") (name "unconnected-(SOM2-PadD19)") (class "Default")
      (node (ref "SOM2") (pin "D19") (pinfunction "D19_D19") (pintype "passive"))
    )
    (net (code "155") (name "unconnected-(SOM2-PadD21)") (class "Default")
      (node (ref "SOM2") (pin "D21") (pinfunction "D21_D21") (pintype "passive"))
    )
    (net (code "156") (name "unconnected-(SOM2-PadD22)") (class "Default")
      (node (ref "SOM2") (pin "D22") (pinfunction "D22_D22") (pintype "passive"))
    )
    (net (code "157") (name "unconnected-(SOM2-PadD24)") (class "Default")
      (node (ref "SOM2") (pin "D24") (pinfunction "D24_D24") (pintype "passive"))
    )
    (net (code "158") (name "unconnected-(SOM2-PadD25)") (class "Default")
      (node (ref "SOM2") (pin "D25") (pinfunction "D25_D25") (pintype "passive"))
    )
    (net (code "159") (name "unconnected-(SOM2-PadD27)") (class "Default")
      (node (ref "SOM2") (pin "D27") (pinfunction "D27_D27") (pintype "passive"))
    )
    (net (code "160") (name "unconnected-(SOM2-PadD28)") (class "Default")
      (node (ref "SOM2") (pin "D28") (pinfunction "D28_D28") (pintype "passive"))
    )
    (net (code "161") (name "unconnected-(SOM2-PadD39)") (class "Default")
      (node (ref "SOM2") (pin "D39") (pinfunction "D39_D39") (pintype "passive"))
    )
    (net (code "162") (name "unconnected-(SOM2-PadD40)") (class "Default")
      (node (ref "SOM2") (pin "D40") (pinfunction "D40_D40") (pintype "passive"))
    )
  )
)
